# RS485.net
KiCad netlist of a schematic drawn in Altium Designer
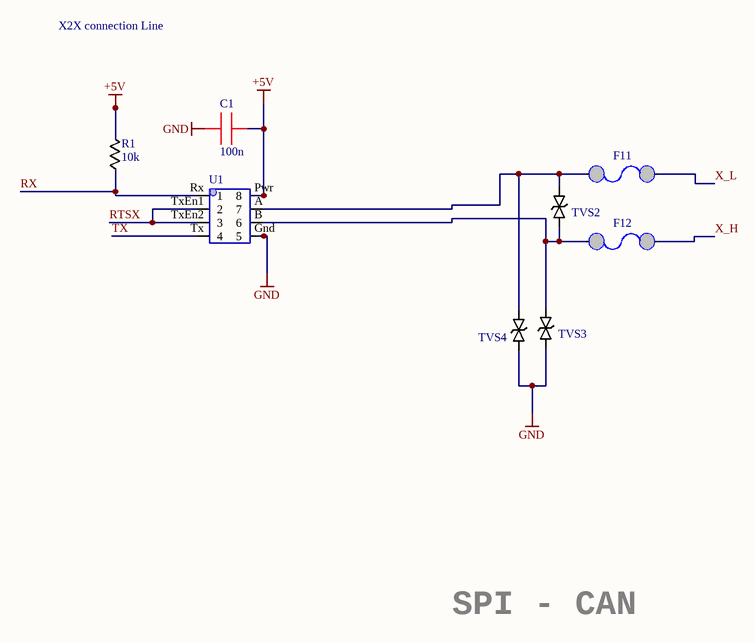
[diagram p0: RS485.SchDoc]

(export (version "E")
  (design (tool "Eeschema 10.0.6"))
  (components
    (comp (ref "C1")
      (value "100n")
      (footprint "0603_Cap")
      (fields (field (name "PART NUMBER") "CC0603ZRY5V9BB104"))
      (libsource (lib "kontr") (part "Capasitor 0805"))
    )
    (comp (ref "F11")
      (value "Fuse PTS")
      (footprint "1210_MF")
      (fields (field (name "PART NUMBER") "MF-USMF005-2"))
      (libsource (lib "kontr") (part "Fuse PTS"))
    )
    (comp (ref "F12")
      (value "Fuse PTS")
      (footprint "1210_MF")
      (fields (field (name "PART NUMBER") "MF-USMF005-2"))
      (libsource (lib "kontr") (part "Fuse PTS"))
    )
    (comp (ref "R1")
      (value "10k")
      (footprint "0603_Res")
      (fields (field (name "PART NUMBER") "RT0603FRE0710KL"))
      (libsource (lib "kontr") (part "Resistor 0805"))
    )
    (comp (ref "TVS2")
      (value "~")
      (footprint "DO-214AC")
      (fields (field (name "PART NUMBER") "SMAJ5.0CA"))
      (libsource (lib "kontr") (part "SMAJ5.0CA"))
    )
    (comp (ref "TVS3")
      (value "~")
      (footprint "DO-214AC")
      (fields (field (name "PART NUMBER") "SMAJ5.0CA"))
      (libsource (lib "kontr") (part "SMAJ5.0CA"))
    )
    (comp (ref "TVS4")
      (value "~")
      (footprint "DO-214AC")
      (fields (field (name "PART NUMBER") "SMAJ5.0CA"))
      (libsource (lib "kontr") (part "SMAJ5.0CA"))
    )
    (comp (ref "U1")
      (value "~")
      (footprint "EIA485")
      (fields (field (name "PART NUMBER") "SN65HVD3082EDR"))
      (libsource (lib "Schlib1") (part "MAX485"))
    )
  )
  (nets
    (net (code "1") (name "+5V") (class "Default")
      (node (ref "C1") (pin "2") (pinfunction "2_2") (pintype "passive"))
      (node (ref "R1") (pin "2") (pintype "passive"))
      (node (ref "U1") (pin "Pwr") (pinfunction "8_Pwr") (pintype "passive"))
    )
    (net (code "2") (name "/RTSX") (class "Default")
      (node (ref "U1") (pin "TxEn1") (pinfunction "2_TxEn1") (pintype "passive"))
      (node (ref "U1") (pin "TxEn2") (pinfunction "3_TxEn2") (pintype "passive"))
    )
    (net (code "3") (name "/RX") (class "Default")
      (node (ref "R1") (pin "1") (pintype "passive"))
      (node (ref "U1") (pin "Rx") (pinfunction "1_Rx") (pintype "passive"))
    )
    (net (code "4") (name "/TX") (class "Default")
      (node (ref "U1") (pin "Tx") (pinfunction "4_Tx") (pintype "passive"))
    )
    (net (code "5") (name "/X_H") (class "Default")
      (node (ref "F12") (pin "1") (pinfunction "1_1") (pintype "passive"))
    )
    (net (code "6") (name "/X_L") (class "Default")
      (node (ref "F11") (pin "1") (pinfunction "1_1") (pintype "passive"))
    )
    (net (code "7") (name "GND") (class "Default")
      (node (ref "C1") (pin "1") (pinfunction "1_1") (pintype "passive"))
      (node (ref "TVS3") (pin "1") (pinfunction "1_1") (pintype "passive"))
      (node (ref "TVS4") (pin "1") (pinfunction "1_1") (pintype "passive"))
      (node (ref "U1") (pin "Gnd") (pinfunction "5_Gnd") (pintype "passive"))
    )
    (net (code "8") (name "Net-(U1-6)") (class "Default")
      (node (ref "F12") (pin "2") (pinfunction "2_2") (pintype "passive"))
      (node (ref "TVS2") (pin "1") (pinfunction "1_1") (pintype "passive"))
      (node (ref "TVS3") (pin "2") (pinfunction "2_2") (pintype "passive"))
      (node (ref "U1") (pin "B") (pinfunction "6_B") (pintype "passive"))
    )
    (net (code "9") (name "Net-(U1-7)") (class "Default")
      (node (ref "F11") (pin "2") (pinfunction "2_2") (pintype "passive"))
      (node (ref "TVS2") (pin "2") (pinfunction "2_2") (pintype "passive"))
      (node (ref "TVS4") (pin "2") (pinfunction "2_2") (pintype "passive"))
      (node (ref "U1") (pin "A") (pinfunction "7_A") (pintype "passive"))
    )
  )
)
